# lm386_nogain_v4.net
KiCad netlist of a schematic drawn in EAGLE
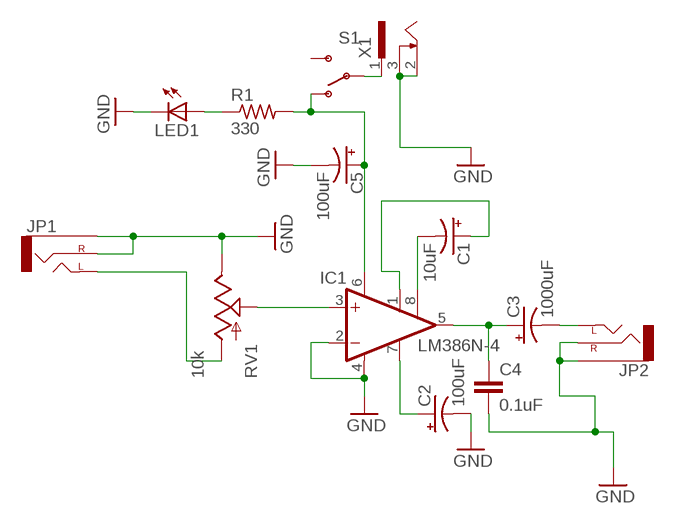
[diagram p0: schematic, sheet 1]

(export (version "E")
  (design (tool "Eeschema 10.0.6"))
  (components
    (comp (ref "C1")
      (value "10uF")
      (footprint "eagle-import:CPOL-RADIAL-10UF-25V")
      (libsource (lib "eagle-import") (part "CAP_POLPTH2"))
    )
    (comp (ref "C2")
      (value "100uF")
      (footprint "eagle-import:CPOL-RADIAL-10UF-25V")
      (libsource (lib "eagle-import") (part "CAP_POLPTH2"))
    )
    (comp (ref "C3")
      (value "1000uF")
      (footprint "eagle-import:CPOL-RADIAL-10UF-25V")
      (libsource (lib "eagle-import") (part "CAP_POLPTH2"))
    )
    (comp (ref "C4")
      (value "0.1uF")
      (footprint "eagle-import:CAP-PTH-SMALL2")
      (libsource (lib "eagle-import") (part "CAPPTH2"))
    )
    (comp (ref "C5")
      (value "100uF")
      (footprint "eagle-import:CPOL-RADIAL-100UF-25V")
      (libsource (lib "eagle-import") (part "100UF-25V-20%(PTH)"))
    )
    (comp (ref "IC1")
      (value "LM386N-4")
      (footprint "eagle-import:DIL08")
      (libsource (lib "eagle-import") (part "LM386?-N4"))
    )
    (comp (ref "JP1")
      (value "AUDIO-JACKPTH")
      (footprint "eagle-import:AUDIO-JACK")
      (libsource (lib "eagle-import") (part "AUDIO-JACKPTH"))
    )
    (comp (ref "JP2")
      (value "AUDIO-JACKPTH")
      (footprint "eagle-import:AUDIO-JACK")
      (libsource (lib "eagle-import") (part "AUDIO-JACKPTH"))
    )
    (comp (ref "LED1")
      (value "LED5MM")
      (footprint "eagle-import:LED5MM")
      (libsource (lib "eagle-import") (part "LED5MM"))
    )
    (comp (ref "R1")
      (value "330")
      (footprint "eagle-import:0204V")
      (libsource (lib "eagle-import") (part "R-US_0204/2V"))
    )
    (comp (ref "RV1")
      (value "10k")
      (footprint "eagle-import:ALPS_POT")
      (libsource (lib "eagle-import") (part "POT"))
    )
    (comp (ref "S1")
      (value "SWITCH-SPDTPTH_LOCK")
      (footprint "eagle-import:SWITCH-SPDT_LOCK.007S")
      (libsource (lib "eagle-import") (part "SWITCH-SPDTPTH_LOCK"))
    )
    (comp (ref "X1")
      (value "SCD-014A")
      (footprint "eagle-import:SCD-014-A")
      (libsource (lib "eagle-import") (part "SCD-014A"))
    )
  )
  (nets
    (net (code "1") (name "GND") (class "Default")
      (node (ref "C2") (pin "2") (pinfunction "-_2") (pintype "passive"))
      (node (ref "C4") (pin "2") (pinfunction "2_2") (pintype "passive"))
      (node (ref "C5") (pin "2") (pinfunction "-_2") (pintype "passive"))
      (node (ref "IC1") (pin "2") (pinfunction "-IN_2") (pintype "input"))
      (node (ref "IC1") (pin "4") (pinfunction "GND_4") (pintype "power_in"))
      (node (ref "JP1") (pin "RING") (pinfunction "RIGHT_RING") (pintype "bidirectional"))
      (node (ref "JP1") (pin "SLEEVE") (pinfunction "SLEEVE_SLEEVE") (pintype "bidirectional"))
      (node (ref "JP2") (pin "RING") (pinfunction "RIGHT_RING") (pintype "bidirectional"))
      (node (ref "JP2") (pin "SLEEVE") (pinfunction "SLEEVE_SLEEVE") (pintype "bidirectional"))
      (node (ref "LED1") (pin "K") (pinfunction "C_K") (pintype "passive"))
      (node (ref "RV1") (pin "P$1") (pinfunction "E_P$1") (pintype "passive"))
      (node (ref "X1") (pin "2") (pinfunction "2_2") (pintype "passive"))
      (node (ref "X1") (pin "3") (pinfunction "3_3") (pintype "passive"))
    )
    (net (code "2") (name "Net-(C1-+)") (class "Default")
      (node (ref "C1") (pin "1") (pinfunction "+_1") (pintype "passive"))
      (node (ref "IC1") (pin "1") (pinfunction "GAIN_1") (pintype "passive"))
    )
    (net (code "3") (name "Net-(C1--)") (class "Default")
      (node (ref "C1") (pin "2") (pinfunction "-_2") (pintype "passive"))
      (node (ref "IC1") (pin "8") (pinfunction "GAIN_8") (pintype "passive"))
    )
    (net (code "4") (name "Net-(C2-+)") (class "Default")
      (node (ref "C2") (pin "1") (pinfunction "+_1") (pintype "passive"))
      (node (ref "IC1") (pin "7") (pinfunction "BYPASS_7") (pintype "passive"))
    )
    (net (code "5") (name "Net-(C3-+)") (class "Default")
      (node (ref "C3") (pin "1") (pinfunction "+_1") (pintype "passive"))
      (node (ref "C4") (pin "1") (pinfunction "1_1") (pintype "passive"))
      (node (ref "IC1") (pin "5") (pinfunction "OUT_5") (pintype "output"))
    )
    (net (code "6") (name "Net-(C3--)") (class "Default")
      (node (ref "C3") (pin "2") (pinfunction "-_2") (pintype "passive"))
      (node (ref "JP2") (pin "TIP") (pinfunction "LEFT_TIP") (pintype "bidirectional"))
    )
    (net (code "7") (name "Net-(C5-+)") (class "Default")
      (node (ref "C5") (pin "1") (pinfunction "+_1") (pintype "passive"))
      (node (ref "IC1") (pin "6") (pinfunction "VS_6") (pintype "power_in"))
      (node (ref "R1") (pin "2") (pinfunction "2_2") (pintype "passive"))
      (node (ref "S1") (pin "1") (pinfunction "O_1") (pintype "passive"))
    )
    (net (code "8") (name "Net-(IC1-+IN)") (class "Default")
      (node (ref "IC1") (pin "3") (pinfunction "+IN_3") (pintype "input"))
      (node (ref "RV1") (pin "P$2") (pinfunction "S_P$2") (pintype "passive"))
    )
    (net (code "9") (name "Net-(JP1-LEFT)") (class "Default")
      (node (ref "JP1") (pin "TIP") (pinfunction "LEFT_TIP") (pintype "bidirectional"))
      (node (ref "RV1") (pin "P$3") (pinfunction "A_P$3") (pintype "passive"))
    )
    (net (code "10") (name "Net-(LED1-PadA)") (class "Default")
      (node (ref "LED1") (pin "A") (pinfunction "A_A") (pintype "passive"))
      (node (ref "R1") (pin "1") (pinfunction "1_1") (pintype "passive"))
    )
    (net (code "11") (name "Net-(S1-P)") (class "Default")
      (node (ref "S1") (pin "2") (pinfunction "P_2") (pintype "passive"))
      (node (ref "X1") (pin "1") (pinfunction "1_1") (pintype "passive"))
    )
    (net (code "12") (name "unconnected-(S1-S-Pad3)") (class "Default")
      (node (ref "S1") (pin "3") (pinfunction "S_3") (pintype "passive"))
    )
  )
)
